# TK512_Optisk_Mottaker.net
KiCad netlist of a schematic drawn in Altium Designer
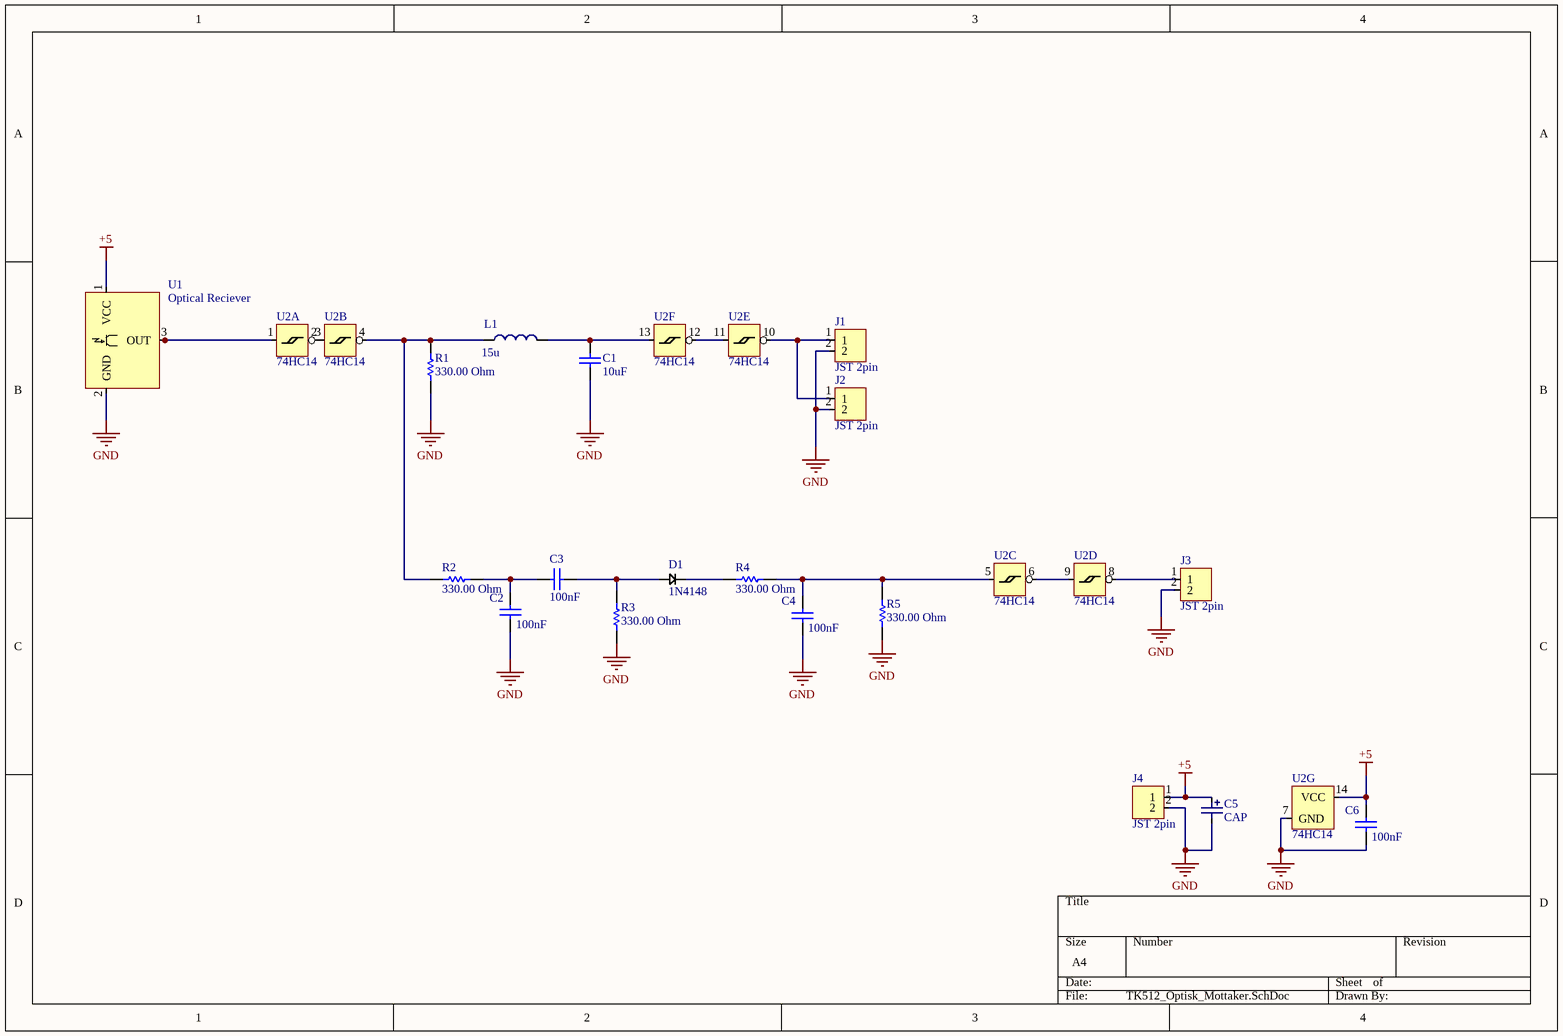
[diagram p0: TK512_Optisk_Mottaker.SchDoc]

(export (version "E")
  (design (tool "Eeschema 10.0.6"))
  (components
    (comp (ref "C1")
      (value "10uF")
      (footprint "CAPC1206(3216)190_L")
      (description "CAP 10uF 25V ±10% 1206 (3216 Metric) Thickness 1.9mm SMD")
      (fields (field (name "TOLERANCE") "±10%") (field (name "Comment") "CAP 10uF 25V 1206(3216)"))
      (libsource (lib "Altium Content Vault") (part "CAP"))
    )
    (comp (ref "C2")
      (value "100nF")
      (footprint "CAPC0805(2012)145_M")
      (description "CAP 100nF 25V ±5% 0805 (2012 Metric) Thickness 1.45mm SMD")
      (fields (field (name "TOLERANCE") "±5%") (field (name "Comment") "CAP 100nF 25V 0805(2012)"))
      (libsource (lib "Altium Content Vault") (part "CAP"))
    )
    (comp (ref "C3")
      (value "100nF")
      (footprint "CAPC0805(2012)145_M")
      (description "CAP 100nF 25V ±5% 0805 (2012 Metric) Thickness 1.45mm SMD")
      (fields (field (name "TOLERANCE") "±5%") (field (name "Comment") "CAP 100nF 25V 0805(2012)"))
      (libsource (lib "Altium Content Vault") (part "CAP"))
    )
    (comp (ref "C4")
      (value "100nF")
      (footprint "CAPC0805(2012)145_M")
      (description "CAP 100nF 25V ±5% 0805 (2012 Metric) Thickness 1.45mm SMD")
      (fields (field (name "TOLERANCE") "±5%") (field (name "Comment") "CAP 100nF 25V 0805(2012)"))
      (libsource (lib "Altium Content Vault") (part "CAP"))
    )
    (comp (ref "C5") (value "CAP") (footprint "CAP 2.5mm") (libsource (lib "Schlib1") (part "CAP")))
    (comp (ref "C6")
      (value "100nF")
      (footprint "CAPC0805(2012)145_M")
      (description "CAP 100nF 25V ±5% 0805 (2012 Metric) Thickness 1.45mm SMD")
      (fields (field (name "TOLERANCE") "±5%") (field (name "Comment") "CAP 100nF 25V 0805(2012)"))
      (libsource (lib "Altium Content Vault") (part "CAP"))
    )
    (comp (ref "D1") (value "1N4148") (footprint "1N4148") (libsource (lib "Schlib1") (part "1N4148")))
    (comp (ref "J1") (value "JST 2pin") (footprint "JST 2pin") (libsource (lib "Schlib1") (part "JST 2pin")))
    (comp (ref "J2") (value "JST 2pin") (footprint "JST 2pin") (libsource (lib "Schlib1") (part "JST 2pin")))
    (comp (ref "J3") (value "JST 2pin") (footprint "JST 2pin") (libsource (lib "Schlib1") (part "JST 2pin")))
    (comp (ref "J4") (value "JST 2pin") (footprint "JST 2pin") (libsource (lib "") (part "JST 2pin_1")))
    (comp (ref "L1")
      (value "15u")
      (footprint "SMD4mm")
      (fields (field (name "Comment") "L"))
      (libsource (lib "Schlib1") (part "L"))
    )
    (comp (ref "R1")
      (value "330.00 Ohm")
      (footprint "RESC0805(2012)_L")
      (description "330R 0.125W 5% 0805 (2012 Metric)  SMD")
      (fields (field (name "TOLERANCE") "5 %") (field (name "POWER") "0.125 W"))
      (libsource (lib "Altium Content Vault") (part "RES"))
    )
    (comp (ref "R2")
      (value "330.00 Ohm")
      (footprint "RESC0805(2012)_L")
      (description "330R 0.125W 5% 0805 (2012 Metric)  SMD")
      (fields (field (name "TOLERANCE") "5 %") (field (name "POWER") "0.125 W"))
      (libsource (lib "Altium Content Vault") (part "RES"))
    )
    (comp (ref "R3")
      (value "330.00 Ohm")
      (footprint "RESC0805(2012)_L")
      (description "330R 0.125W 5% 0805 (2012 Metric)  SMD")
      (fields (field (name "TOLERANCE") "5 %") (field (name "POWER") "0.125 W"))
      (libsource (lib "Altium Content Vault") (part "RES"))
    )
    (comp (ref "R4")
      (value "330.00 Ohm")
      (footprint "RESC0805(2012)_L")
      (description "330R 0.125W 5% 0805 (2012 Metric)  SMD")
      (fields (field (name "TOLERANCE") "5 %") (field (name "POWER") "0.125 W"))
      (libsource (lib "Altium Content Vault") (part "RES"))
    )
    (comp (ref "R5")
      (value "330.00 Ohm")
      (footprint "RESC0805(2012)_L")
      (description "330R 0.125W 5% 0805 (2012 Metric)  SMD")
      (fields (field (name "TOLERANCE") "5 %") (field (name "POWER") "0.125 W"))
      (libsource (lib "Altium Content Vault") (part "RES"))
    )
    (comp (ref "U1")
      (value "Optical Reciever")
      (footprint "GP1FAV50TK")
      (libsource (lib "Schlib1") (part "Otical Reciever"))
    )
    (comp (ref "U2") (value "74HC14") (footprint "SOP14") (libsource (lib "Schlib1") (part "74HC14")))
  )
  (nets
    (net (code "1") (name "+5") (class "Default")
      (node (ref "C5") (pin "2") (pinfunction "2_2") (pintype "passive"))
      (node (ref "C6") (pin "2") (pinfunction "2_2") (pintype "passive"))
      (node (ref "J4") (pin "1") (pinfunction "1_1") (pintype "passive"))
      (node (ref "U1") (pin "1") (pinfunction "VCC_1") (pintype "passive"))
      (node (ref "U2") (pin "14") (pinfunction "VCC_14") (pintype "passive"))
    )
    (net (code "2") (name "GND") (class "Default")
      (node (ref "C1") (pin "1") (pinfunction "1_1") (pintype "passive"))
      (node (ref "C2") (pin "1") (pinfunction "1_1") (pintype "passive"))
      (node (ref "C4") (pin "1") (pinfunction "1_1") (pintype "passive"))
      (node (ref "C5") (pin "1") (pinfunction "1_1") (pintype "passive"))
      (node (ref "C6") (pin "1") (pinfunction "1_1") (pintype "passive"))
      (node (ref "J1") (pin "2") (pinfunction "2_2") (pintype "passive"))
      (node (ref "J2") (pin "2") (pinfunction "2_2") (pintype "passive"))
      (node (ref "J3") (pin "2") (pinfunction "2_2") (pintype "passive"))
      (node (ref "J4") (pin "2") (pinfunction "2_2") (pintype "passive"))
      (node (ref "R1") (pin "2") (pinfunction "2_2") (pintype "passive"))
      (node (ref "R3") (pin "1") (pinfunction "1_1") (pintype "passive"))
      (node (ref "R5") (pin "1") (pinfunction "1_1") (pintype "passive"))
      (node (ref "U1") (pin "2") (pinfunction "GND_2") (pintype "passive"))
      (node (ref "U2") (pin "7") (pinfunction "GND_7") (pintype "passive"))
    )
    (net (code "3") (name "Net-(C1-Pad2)") (class "Default")
      (node (ref "C1") (pin "2") (pinfunction "2_2") (pintype "passive"))
      (node (ref "L1") (pin "2") (pinfunction "2_2") (pintype "passive"))
      (node (ref "U2") (pin "13") (pinfunction "13_13") (pintype "passive"))
    )
    (net (code "4") (name "Net-(C2-Pad2)") (class "Default")
      (node (ref "C2") (pin "2") (pinfunction "2_2") (pintype "passive"))
      (node (ref "C3") (pin "2") (pinfunction "2_2") (pintype "passive"))
      (node (ref "R2") (pin "2") (pinfunction "2_2") (pintype "passive"))
    )
    (net (code "5") (name "Net-(C3-Pad1)") (class "Default")
      (node (ref "C3") (pin "1") (pinfunction "1_1") (pintype "passive"))
      (node (ref "D1") (pin "A") (pinfunction "A_A") (pintype "passive"))
      (node (ref "R3") (pin "2") (pinfunction "2_2") (pintype "passive"))
    )
    (net (code "6") (name "Net-(C4-Pad2)") (class "Default")
      (node (ref "C4") (pin "2") (pinfunction "2_2") (pintype "passive"))
      (node (ref "R4") (pin "2") (pinfunction "2_2") (pintype "passive"))
      (node (ref "R5") (pin "2") (pinfunction "2_2") (pintype "passive"))
      (node (ref "U2") (pin "5") (pinfunction "5_5") (pintype "passive"))
    )
    (net (code "7") (name "Net-(D1-PadK)") (class "Default")
      (node (ref "D1") (pin "K") (pinfunction "K_K") (pintype "passive"))
      (node (ref "R4") (pin "1") (pinfunction "1_1") (pintype "passive"))
    )
    (net (code "8") (name "Net-(J1-Pad1)") (class "Default")
      (node (ref "J1") (pin "1") (pinfunction "1_1") (pintype "passive"))
      (node (ref "J2") (pin "1") (pinfunction "1_1") (pintype "passive"))
      (node (ref "U2") (pin "10") (pinfunction "10_10") (pintype "passive"))
    )
    (net (code "9") (name "Net-(J3-Pad1)") (class "Default")
      (node (ref "J3") (pin "1") (pinfunction "1_1") (pintype "passive"))
      (node (ref "U2") (pin "8") (pinfunction "8_8") (pintype "passive"))
    )
    (net (code "10") (name "Net-(L1-Pad1)") (class "Default")
      (node (ref "L1") (pin "1") (pinfunction "1_1") (pintype "passive"))
      (node (ref "R1") (pin "1") (pinfunction "1_1") (pintype "passive"))
      (node (ref "R2") (pin "1") (pinfunction "1_1") (pintype "passive"))
      (node (ref "U2") (pin "4") (pinfunction "4_4") (pintype "passive"))
    )
    (net (code "11") (name "Net-(U1-OUT)") (class "Default")
      (node (ref "U1") (pin "3") (pinfunction "OUT_3") (pintype "passive"))
      (node (ref "U2") (pin "1") (pinfunction "1_1") (pintype "passive"))
    )
    (net (code "12") (name "Net-(U2-Pad2)") (class "Default")
      (node (ref "U2") (pin "2") (pinfunction "2_2") (pintype "passive"))
      (node (ref "U2") (pin "3") (pinfunction "3_3") (pintype "passive"))
    )
    (net (code "13") (name "Net-(U2-Pad6)") (class "Default")
      (node (ref "U2") (pin "6") (pinfunction "6_6") (pintype "passive"))
      (node (ref "U2") (pin "9") (pinfunction "9_9") (pintype "passive"))
    )
    (net (code "14") (name "Net-(U2-Pad11)") (class "Default")
      (node (ref "U2") (pin "11") (pinfunction "11_11") (pintype "passive"))
      (node (ref "U2") (pin "12") (pinfunction "12_12") (pintype "passive"))
    )
  )
)
